# INFRARED.net
KiCad netlist of a schematic drawn in Altium Designer
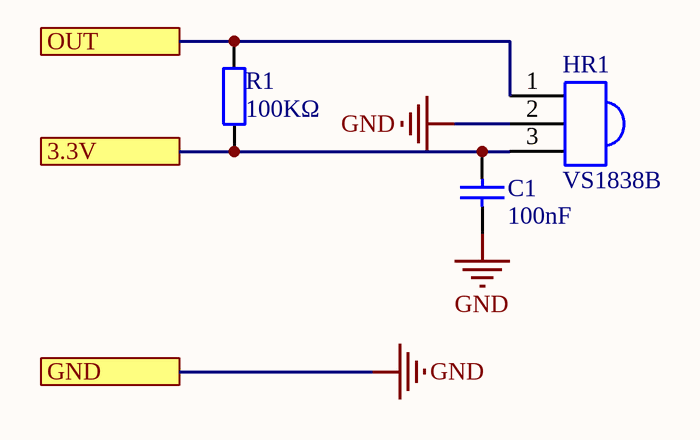
[diagram p0: INFRARED.SchDoc]

(export (version "E")
  (design (tool "Eeschema 10.0.6"))
  (components
    (comp (ref "C1")
      (value "100nF")
      (footprint "LC-0603_C")
      (description "贴片电容")
      (libsource (lib "Miscellaneous Devices LC") (part "0603 100nF (104) 10% 50V"))
    )
    (comp (ref "HR1")
      (value "VS1838B")
      (footprint "VS1838B-A")
      (description "红外接收头")
      (fields (field (name "版权归属") "封装库来自淘宝 ID：黄晶宝石"))
      (libsource (lib "1.2 - 传感元件") (part "VS1838B"))
    )
    (comp (ref "R1")
      (value "100KΩ")
      (footprint "LC-0603_R")
      (description "贴片电阻")
      (libsource (lib "Miscellaneous Devices LC") (part "0603 100KΩ (1003) 1%"))
    )
  )
  (nets
    (net (code "1") (name "/3.3V") (class "Default")
      (node (ref "C1") (pin "2") (pinfunction "2_2") (pintype "passive"))
      (node (ref "HR1") (pin "3") (pinfunction "E_3") (pintype "passive"))
      (node (ref "R1") (pin "2") (pinfunction "2_2") (pintype "passive"))
    )
    (net (code "2") (name "/OUT") (class "Default")
      (node (ref "HR1") (pin "1") (pinfunction "A_1") (pintype "passive"))
      (node (ref "R1") (pin "1") (pinfunction "1_1") (pintype "passive"))
    )
    (net (code "3") (name "GND") (class "Default")
      (node (ref "C1") (pin "1") (pinfunction "1_1") (pintype "passive"))
      (node (ref "HR1") (pin "2") (pinfunction "K_2") (pintype "passive"))
    )
  )
)
